# CONNECTOR.net
KiCad netlist of a schematic drawn in Altium Designer
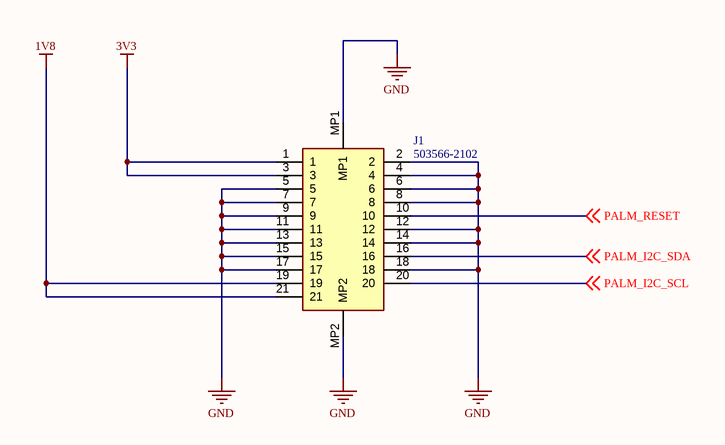
[diagram p0: CONNECTOR.SchDoc]

(export (version "E")
  (design (tool "Eeschema 10.0.6"))
  (components
    (comp (ref "J1")
      (value "503566-2102")
      (footprint "SamacSys:5035662102")
      (description "Connector")
      (fields (field (name "MOUSER PART NUMBER") "538-503566-2102"))
      (libsource (lib "*") (part "503566-2102"))
    )
  )
  (nets
    (net (code "1") (name "1V8") (class "Default")
      (node (ref "J1") (pin "19") (pinfunction "19_19") (pintype "passive"))
      (node (ref "J1") (pin "21") (pinfunction "21_21") (pintype "passive"))
    )
    (net (code "2") (name "3V3") (class "Default")
      (node (ref "J1") (pin "1") (pinfunction "1_1") (pintype "passive"))
      (node (ref "J1") (pin "3") (pinfunction "3_3") (pintype "passive"))
    )
    (net (code "3") (name "GND") (class "Default")
      (node (ref "J1") (pin "11") (pinfunction "11_11") (pintype "passive"))
      (node (ref "J1") (pin "12") (pinfunction "12_12") (pintype "passive"))
      (node (ref "J1") (pin "13") (pinfunction "13_13") (pintype "passive"))
      (node (ref "J1") (pin "14") (pinfunction "14_14") (pintype "passive"))
      (node (ref "J1") (pin "15") (pinfunction "15_15") (pintype "passive"))
      (node (ref "J1") (pin "17") (pinfunction "17_17") (pintype "passive"))
      (node (ref "J1") (pin "18") (pinfunction "18_18") (pintype "passive"))
      (node (ref "J1") (pin "2") (pinfunction "2_2") (pintype "passive"))
      (node (ref "J1") (pin "4") (pinfunction "4_4") (pintype "passive"))
      (node (ref "J1") (pin "5") (pinfunction "5_5") (pintype "passive"))
      (node (ref "J1") (pin "6") (pinfunction "6_6") (pintype "passive"))
      (node (ref "J1") (pin "7") (pinfunction "7_7") (pintype "passive"))
      (node (ref "J1") (pin "8") (pinfunction "8_8") (pintype "passive"))
      (node (ref "J1") (pin "9") (pinfunction "9_9") (pintype "passive"))
      (node (ref "J1") (pin "MP1") (pinfunction "MP1_MP1") (pintype "passive"))
      (node (ref "J1") (pin "MP2") (pinfunction "MP2_MP2") (pintype "passive"))
    )
    (net (code "4") (name "PALM_I2C_SCL") (class "Default")
      (node (ref "J1") (pin "20") (pinfunction "20_20") (pintype "passive"))
    )
    (net (code "5") (name "PALM_I2C_SDA") (class "Default")
      (node (ref "J1") (pin "16") (pinfunction "16_16") (pintype "passive"))
    )
    (net (code "6") (name "PALM_RESET") (class "Default")
      (node (ref "J1") (pin "10") (pinfunction "10_10") (pintype "passive"))
    )
  )
)
